# Carte_alim_Mark1.net
KiCad netlist of a schematic drawn in EAGLE
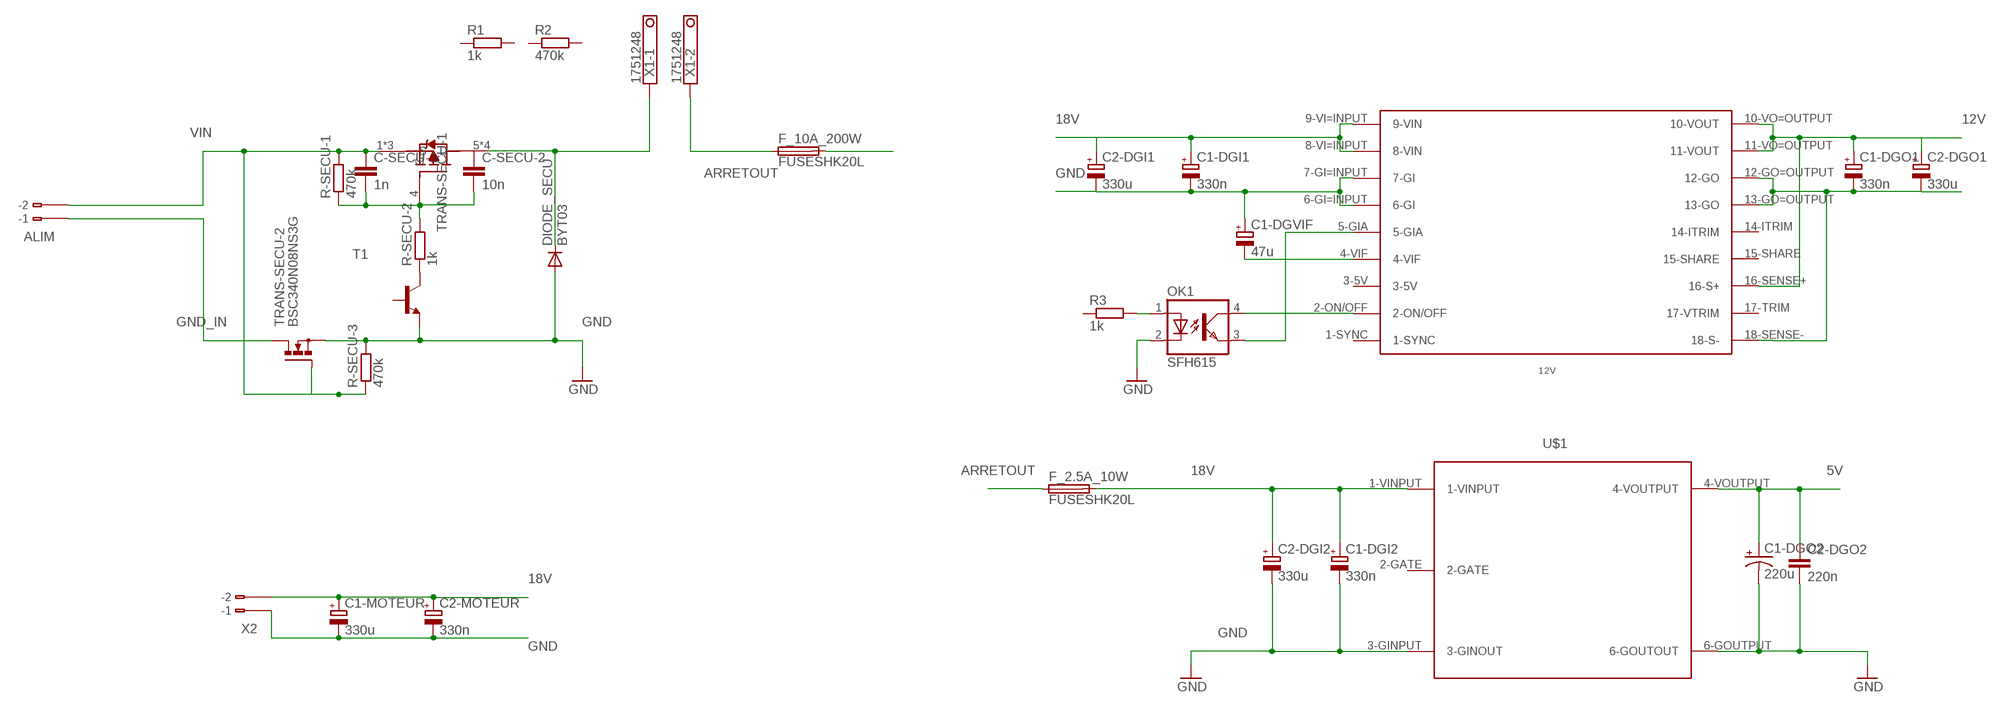
[diagram p0: schematic, sheet 1]

(export (version "E")
  (design (tool "Eeschema 10.0.6"))
  (components
    (comp (ref "12V")
      (value "MGDS200MGDS200")
      (footprint "eagle-import:MGDS200")
      (libsource (lib "eagle-import") (part "MGDS200MGDS200"))
    )
    (comp (ref "ALIM")
      (value "233-102")
      (footprint "eagle-import:233-102")
      (fields
        (field (name "MPN") "233-102")
        (field (name "OC_FARNELL") "unknown")
        (field (name "OC_NEWARK") "28K9044")
      )
      (libsource (lib "eagle-import") (part "233-102"))
    )
    (comp (ref "C-SECU-1")
      (value "1n")
      (footprint "eagle-import:C025-024X044")
      (libsource (lib "eagle-import") (part "C-EU025-024X044"))
    )
    (comp (ref "C-SECU-2")
      (value "10n")
      (footprint "eagle-import:C075-032X103")
      (libsource (lib "eagle-import") (part "C-EU075-032X103"))
    )
    (comp (ref "C1-DGI1")
      (value "330n")
      (footprint "eagle-import:E2-5")
      (libsource (lib "eagle-import") (part "CPOL-EUE2-5"))
    )
    (comp (ref "C1-DGI2")
      (value "330n")
      (footprint "eagle-import:E2-5")
      (libsource (lib "eagle-import") (part "CPOL-EUE2-5"))
    )
    (comp (ref "C1-DGO1")
      (value "330n")
      (footprint "eagle-import:E2-5")
      (libsource (lib "eagle-import") (part "CPOL-EUE2-5"))
    )
    (comp (ref "C1-DGO2")
      (value "220u")
      (footprint "eagle-import:085CS_1AW")
      (libsource (lib "eagle-import") (part "CPOL-US085CS-1AW"))
    )
    (comp (ref "C1-DGVIF")
      (value "47u")
      (footprint "eagle-import:E2-5")
      (libsource (lib "eagle-import") (part "CPOL-EUE2-5"))
    )
    (comp (ref "C1-MOTEUR")
      (value "330u")
      (footprint "eagle-import:E3,5-10")
      (libsource (lib "eagle-import") (part "CPOL-EUE3.5-10"))
    )
    (comp (ref "C2-DGI1")
      (value "330u")
      (footprint "eagle-import:E3,5-10")
      (libsource (lib "eagle-import") (part "CPOL-EUE3.5-10"))
    )
    (comp (ref "C2-DGI2")
      (value "330u")
      (footprint "eagle-import:E3,5-10")
      (libsource (lib "eagle-import") (part "CPOL-EUE3.5-10"))
    )
    (comp (ref "C2-DGO1")
      (value "330u")
      (footprint "eagle-import:E3,5-10")
      (libsource (lib "eagle-import") (part "CPOL-EUE3.5-10"))
    )
    (comp (ref "C2-DGO2")
      (value "220n")
      (footprint "eagle-import:C2012")
      (libsource (lib "eagle-import") (part "C-EUC2012"))
    )
    (comp (ref "C2-MOTEUR")
      (value "330n")
      (footprint "eagle-import:E2-5")
      (libsource (lib "eagle-import") (part "CPOL-EUE2-5"))
    )
    (comp (ref "DIODE_SECU")
      (value "BYT03")
      (footprint "eagle-import:DO27-15")
      (libsource (lib "eagle-import") (part "BYT03"))
    )
    (comp (ref "F_2.5A_10W")
      (value "FUSESHK20L")
      (footprint "eagle-import:SHK20L")
      (fields (field (name "OC_FARNELL") "unknown") (field (name "OC_NEWARK") "unknown"))
      (libsource (lib "eagle-import") (part "FUSESHK20L"))
    )
    (comp (ref "F_10A_200W")
      (value "FUSESHK20L")
      (footprint "eagle-import:SHK20L")
      (libsource (lib "eagle-import") (part "FUSESHK20L"))
    )
    (comp (ref "OK1")
      (value "SFH615")
      (footprint "eagle-import:DIL04")
      (fields (field (name "MPN") "SFH615A-2"))
      (libsource (lib "eagle-import") (part "SFH615"))
    )
    (comp (ref "R-SECU-1")
      (value "470k")
      (footprint "eagle-import:0207_7")
      (libsource (lib "eagle-import") (part "R-EU_0207/7"))
    )
    (comp (ref "R-SECU-2")
      (value "1k")
      (footprint "eagle-import:0207_7")
      (libsource (lib "eagle-import") (part "R-EU_0207/7"))
    )
    (comp (ref "R-SECU-3")
      (value "470k")
      (footprint "eagle-import:0207_7")
      (libsource (lib "eagle-import") (part "R-EU_0207/7"))
    )
    (comp (ref "R1")
      (value "1k")
      (footprint "eagle-import:R2012")
      (libsource (lib "eagle-import") (part "R-EU_R2012"))
    )
    (comp (ref "R2")
      (value "470k")
      (footprint "eagle-import:R2012")
      (libsource (lib "eagle-import") (part "R-EU_R2012"))
    )
    (comp (ref "R3")
      (value "1k")
      (footprint "eagle-import:R2012")
      (libsource (lib "eagle-import") (part "R-EU_R2012"))
    )
    (comp (ref "T1")
      (value "BF844-NPN-TO92-CBE")
      (footprint "eagle-import:TO92-CBE")
      (libsource (lib "eagle-import") (part "-NPN-TO92-CBEBF844"))
    )
    (comp (ref "TRANS-SECU-1")
      (value "BSC080PG-TDSON")
      (footprint "eagle-import:PG-TDSON-8")
      (libsource (lib "eagle-import") (part "BSC080PG-TDSON"))
    )
    (comp (ref "TRANS-SECU-2")
      (value "BSC340N08NS3G")
      (footprint "eagle-import:PG-TDSON-8")
      (libsource (lib "eagle-import") (part "BSC340N08NS3G"))
    )
    (comp (ref "U$1")
      (value "MGDS10SINGLE")
      (footprint "eagle-import:MGDS10")
      (libsource (lib "eagle-import") (part "MGDS10SINGLE"))
    )
    (comp (ref "X1")
      (value "1751248")
      (footprint "eagle-import:1751248")
      (libsource (lib "eagle-import") (part "1751248"))
    )
    (comp (ref "X2")
      (value "233-102")
      (footprint "eagle-import:233-102")
      (libsource (lib "eagle-import") (part "233-102"))
    )
  )
  (nets
    (net (code "1") (name "/5V") (class "Default")
      (node (ref "C1-DGO2") (pin "+") (pinfunction "+_+") (pintype "passive"))
      (node (ref "C2-DGO2") (pin "1") (pinfunction "1_1") (pintype "passive"))
      (node (ref "U$1") (pin "4-VOUTPUT") (pinfunction "4-VOUTPUT_4-VOUTPUT") (pintype "bidirectional"))
    )
    (net (code "2") (name "/12V") (class "Default")
      (node (ref "12V") (pin "10-VO=OUTPUT") (pinfunction "10-VOUT_10-VO=OUTPUT") (pintype "bidirectional"))
      (node (ref "12V") (pin "11-VO=OUTPUT") (pinfunction "11-VOUT_11-VO=OUTPUT") (pintype "bidirectional"))
      (node (ref "12V") (pin "16-SENSE+") (pinfunction "16-S+_16-SENSE+") (pintype "bidirectional"))
      (node (ref "C1-DGO1") (pin "+") (pinfunction "+_+") (pintype "passive"))
      (node (ref "C2-DGO1") (pin "+") (pinfunction "+_+") (pintype "passive"))
    )
    (net (code "3") (name "/18V") (class "Default")
      (node (ref "12V") (pin "8-VI=INPUT") (pinfunction "8-VIN_8-VI=INPUT") (pintype "bidirectional"))
      (node (ref "12V") (pin "9-VI=INPUT") (pinfunction "9-VIN_9-VI=INPUT") (pintype "bidirectional"))
      (node (ref "C1-DGI1") (pin "+") (pinfunction "+_+") (pintype "passive"))
      (node (ref "C1-DGI2") (pin "+") (pinfunction "+_+") (pintype "passive"))
      (node (ref "C1-MOTEUR") (pin "+") (pinfunction "+_+") (pintype "passive"))
      (node (ref "C2-DGI1") (pin "+") (pinfunction "+_+") (pintype "passive"))
      (node (ref "C2-DGI2") (pin "+") (pinfunction "+_+") (pintype "passive"))
      (node (ref "C2-MOTEUR") (pin "+") (pinfunction "+_+") (pintype "passive"))
      (node (ref "F_10A_200W") (pin "2A") (pinfunction "2_2A") (pintype "passive"))
      (node (ref "F_2.5A_10W") (pin "2A") (pinfunction "2_2A") (pintype "passive"))
      (node (ref "U$1") (pin "1-VINPUT") (pinfunction "1-VINPUT_1-VINPUT") (pintype "bidirectional"))
      (node (ref "X2") (pin "B2") (pinfunction "B-2_B2") (pintype "passive"))
    )
    (net (code "4") (name "/ARRETOUT") (class "Default")
      (node (ref "F_10A_200W") (pin "1A") (pinfunction "1_1A") (pintype "passive"))
      (node (ref "F_2.5A_10W") (pin "1A") (pinfunction "1_1A") (pintype "passive"))
      (node (ref "X1") (pin "2") (pinfunction "K_2") (pintype "passive"))
    )
    (net (code "5") (name "/GND_IN") (class "Default")
      (node (ref "ALIM") (pin "B1") (pinfunction "B-1_B1") (pintype "passive"))
      (node (ref "TRANS-SECU-2") (pin "5") (pinfunction "D_5") (pintype "passive"))
      (node (ref "TRANS-SECU-2") (pin "6") (pinfunction "D_6") (pintype "passive"))
      (node (ref "TRANS-SECU-2") (pin "7") (pinfunction "D_7") (pintype "passive"))
      (node (ref "TRANS-SECU-2") (pin "8") (pinfunction "D_8") (pintype "passive"))
    )
    (net (code "6") (name "/VIN") (class "Default")
      (node (ref "ALIM") (pin "B2") (pinfunction "B-2_B2") (pintype "passive"))
      (node (ref "C-SECU-1") (pin "1") (pinfunction "1_1") (pintype "passive"))
      (node (ref "R-SECU-1") (pin "2") (pinfunction "2_2") (pintype "passive"))
      (node (ref "R-SECU-3") (pin "1") (pinfunction "1_1") (pintype "passive"))
      (node (ref "TRANS-SECU-1") (pin "1") (pinfunction "S_1") (pintype "bidirectional"))
      (node (ref "TRANS-SECU-1") (pin "2") (pinfunction "S_2") (pintype "bidirectional"))
      (node (ref "TRANS-SECU-1") (pin "3") (pinfunction "S_3") (pintype "bidirectional"))
      (node (ref "TRANS-SECU-2") (pin "4") (pinfunction "G_4") (pintype "passive"))
    )
    (net (code "7") (name "GND") (class "Default")
      (node (ref "12V") (pin "12-GO=OUTPUT") (pinfunction "12-GO_12-GO=OUTPUT") (pintype "bidirectional"))
      (node (ref "12V") (pin "13-GO=OUTPUT") (pinfunction "13-GO_13-GO=OUTPUT") (pintype "bidirectional"))
      (node (ref "12V") (pin "18-SENSE-") (pinfunction "18-S-_18-SENSE-") (pintype "bidirectional"))
      (node (ref "12V") (pin "6-GI=INPUT") (pinfunction "6-GI_6-GI=INPUT") (pintype "bidirectional"))
      (node (ref "12V") (pin "7-GI=INPUT") (pinfunction "7-GI_7-GI=INPUT") (pintype "bidirectional"))
      (node (ref "C1-DGI1") (pin "-") (pinfunction "-_-") (pintype "passive"))
      (node (ref "C1-DGI2") (pin "-") (pinfunction "-_-") (pintype "passive"))
      (node (ref "C1-DGO1") (pin "-") (pinfunction "-_-") (pintype "passive"))
      (node (ref "C1-DGO2") (pin "-") (pinfunction "-_-") (pintype "passive"))
      (node (ref "C1-DGVIF") (pin "+") (pinfunction "+_+") (pintype "passive"))
      (node (ref "C1-MOTEUR") (pin "-") (pinfunction "-_-") (pintype "passive"))
      (node (ref "C2-DGI1") (pin "-") (pinfunction "-_-") (pintype "passive"))
      (node (ref "C2-DGI2") (pin "-") (pinfunction "-_-") (pintype "passive"))
      (node (ref "C2-DGO1") (pin "-") (pinfunction "-_-") (pintype "passive"))
      (node (ref "C2-DGO2") (pin "2") (pinfunction "2_2") (pintype "passive"))
      (node (ref "C2-MOTEUR") (pin "-") (pinfunction "-_-") (pintype "passive"))
      (node (ref "DIODE_SECU") (pin "A") (pinfunction "A_A") (pintype "passive"))
      (node (ref "OK1") (pin "2") (pinfunction "C_2") (pintype "passive"))
      (node (ref "R-SECU-3") (pin "2") (pinfunction "2_2") (pintype "passive"))
      (node (ref "T1") (pin "E") (pinfunction "E_E") (pintype "passive"))
      (node (ref "TRANS-SECU-2") (pin "1") (pinfunction "S_1") (pintype "passive"))
      (node (ref "TRANS-SECU-2") (pin "2") (pinfunction "S_2") (pintype "passive"))
      (node (ref "TRANS-SECU-2") (pin "3") (pinfunction "S_3") (pintype "passive"))
      (node (ref "U$1") (pin "3-GINPUT") (pinfunction "3-GINOUT_3-GINPUT") (pintype "bidirectional"))
      (node (ref "U$1") (pin "6-GOUTPUT") (pinfunction "6-GOUTOUT_6-GOUTPUT") (pintype "bidirectional"))
      (node (ref "X2") (pin "B1") (pinfunction "B-1_B1") (pintype "passive"))
    )
    (net (code "8") (name "Net-(12V-Pad4-VIF)") (class "Default")
      (node (ref "12V") (pin "4-VIF") (pinfunction "4-VIF_4-VIF") (pintype "bidirectional"))
      (node (ref "C1-DGVIF") (pin "-") (pinfunction "-_-") (pintype "passive"))
    )
    (net (code "9") (name "Net-(OK1-A)") (class "Default")
      (node (ref "OK1") (pin "1") (pinfunction "A_1") (pintype "passive"))
      (node (ref "R3") (pin "2") (pinfunction "2_2") (pintype "passive"))
    )
    (net (code "10") (name "Net-(OK1-COL)") (class "Default")
      (node (ref "12V") (pin "2-ON/OFF") (pinfunction "2-ON/OFF_2-ON/OFF") (pintype "bidirectional"))
      (node (ref "OK1") (pin "4") (pinfunction "COL_4") (pintype "passive"))
    )
    (net (code "11") (name "Net-(OK1-EMIT)") (class "Default")
      (node (ref "12V") (pin "5-GIA") (pinfunction "5-GIA_5-GIA") (pintype "bidirectional"))
      (node (ref "OK1") (pin "3") (pinfunction "EMIT_3") (pintype "passive"))
    )
    (net (code "12") (name "Net-(R-SECU-2-Pad1)") (class "Default")
      (node (ref "R-SECU-2") (pin "1") (pinfunction "1_1") (pintype "passive"))
      (node (ref "T1") (pin "C") (pinfunction "C_C") (pintype "passive"))
    )
    (net (code "13") (name "Net-(TRANS-SECU-1-G)") (class "Default")
      (node (ref "C-SECU-1") (pin "2") (pinfunction "2_2") (pintype "passive"))
      (node (ref "C-SECU-2") (pin "2") (pinfunction "2_2") (pintype "passive"))
      (node (ref "R-SECU-1") (pin "1") (pinfunction "1_1") (pintype "passive"))
      (node (ref "R-SECU-2") (pin "2") (pinfunction "2_2") (pintype "passive"))
      (node (ref "TRANS-SECU-1") (pin "4") (pinfunction "G_4") (pintype "bidirectional"))
    )
    (net (code "14") (name "Net-(X1A-K)") (class "Default")
      (node (ref "DIODE_SECU") (pin "C") (pinfunction "C_C") (pintype "passive"))
      (node (ref "TRANS-SECU-1") (pin "5") (pinfunction "D_5") (pintype "bidirectional"))
      (node (ref "TRANS-SECU-1") (pin "6") (pinfunction "D_6") (pintype "bidirectional"))
      (node (ref "TRANS-SECU-1") (pin "7") (pinfunction "D_7") (pintype "bidirectional"))
      (node (ref "TRANS-SECU-1") (pin "8") (pinfunction "D_8") (pintype "bidirectional"))
      (node (ref "X1") (pin "1") (pinfunction "K_1") (pintype "passive"))
    )
    (net (code "15") (name "unconnected-(12V-17-VTRIM-Pad17-TRIM)") (class "Default")
      (node (ref "12V") (pin "17-TRIM") (pinfunction "17-VTRIM_17-TRIM") (pintype "bidirectional"))
    )
    (net (code "16") (name "unconnected-(12V-Pad1-SYNC)") (class "Default")
      (node (ref "12V") (pin "1-SYNC") (pinfunction "1-SYNC_1-SYNC") (pintype "bidirectional"))
    )
    (net (code "17") (name "unconnected-(12V-Pad3-5V)") (class "Default")
      (node (ref "12V") (pin "3-5V") (pinfunction "3-5V_3-5V") (pintype "bidirectional"))
    )
    (net (code "18") (name "unconnected-(12V-Pad14-ITRIM)") (class "Default")
      (node (ref "12V") (pin "14-ITRIM") (pinfunction "14-ITRIM_14-ITRIM") (pintype "bidirectional"))
    )
    (net (code "19") (name "unconnected-(12V-Pad15-SHARE)") (class "Default")
      (node (ref "12V") (pin "15-SHARE") (pinfunction "15-SHARE_15-SHARE") (pintype "bidirectional"))
    )
    (net (code "20") (name "unconnected-(ALIM--1-PadA1)") (class "Default")
      (node (ref "ALIM") (pin "A1") (pinfunction "-1_A1") (pintype "passive"))
    )
    (net (code "21") (name "unconnected-(ALIM--2-PadA2)") (class "Default")
      (node (ref "ALIM") (pin "A2") (pinfunction "-2_A2") (pintype "passive"))
    )
    (net (code "22") (name "unconnected-(C-SECU-2-Pad1)") (class "Default")
      (node (ref "C-SECU-2") (pin "1") (pinfunction "1_1") (pintype "passive"))
    )
    (net (code "23") (name "unconnected-(R1-Pad1)") (class "Default")
      (node (ref "R1") (pin "1") (pinfunction "1_1") (pintype "passive"))
    )
    (net (code "24") (name "unconnected-(R1-Pad2)") (class "Default")
      (node (ref "R1") (pin "2") (pinfunction "2_2") (pintype "passive"))
    )
    (net (code "25") (name "unconnected-(R2-Pad1)") (class "Default")
      (node (ref "R2") (pin "1") (pinfunction "1_1") (pintype "passive"))
    )
    (net (code "26") (name "unconnected-(R2-Pad2)") (class "Default")
      (node (ref "R2") (pin "2") (pinfunction "2_2") (pintype "passive"))
    )
    (net (code "27") (name "unconnected-(R3-Pad1)") (class "Default")
      (node (ref "R3") (pin "1") (pinfunction "1_1") (pintype "passive"))
    )
    (net (code "28") (name "unconnected-(T1-PadB)") (class "Default")
      (node (ref "T1") (pin "B") (pinfunction "B_B") (pintype "passive"))
    )
    (net (code "29") (name "unconnected-(U$1-Pad2-GATE)") (class "Default")
      (node (ref "U$1") (pin "2-GATE") (pinfunction "2-GATE_2-GATE") (pintype "bidirectional"))
    )
    (net (code "30") (name "unconnected-(X2--1-PadA1)") (class "Default")
      (node (ref "X2") (pin "A1") (pinfunction "-1_A1") (pintype "passive"))
    )
    (net (code "31") (name "unconnected-(X2--2-PadA2)") (class "Default")
      (node (ref "X2") (pin "A2") (pinfunction "-2_A2") (pintype "passive"))
    )
  )
)
